# GSM_Schematic.net
KiCad netlist of a schematic drawn in EAGLE
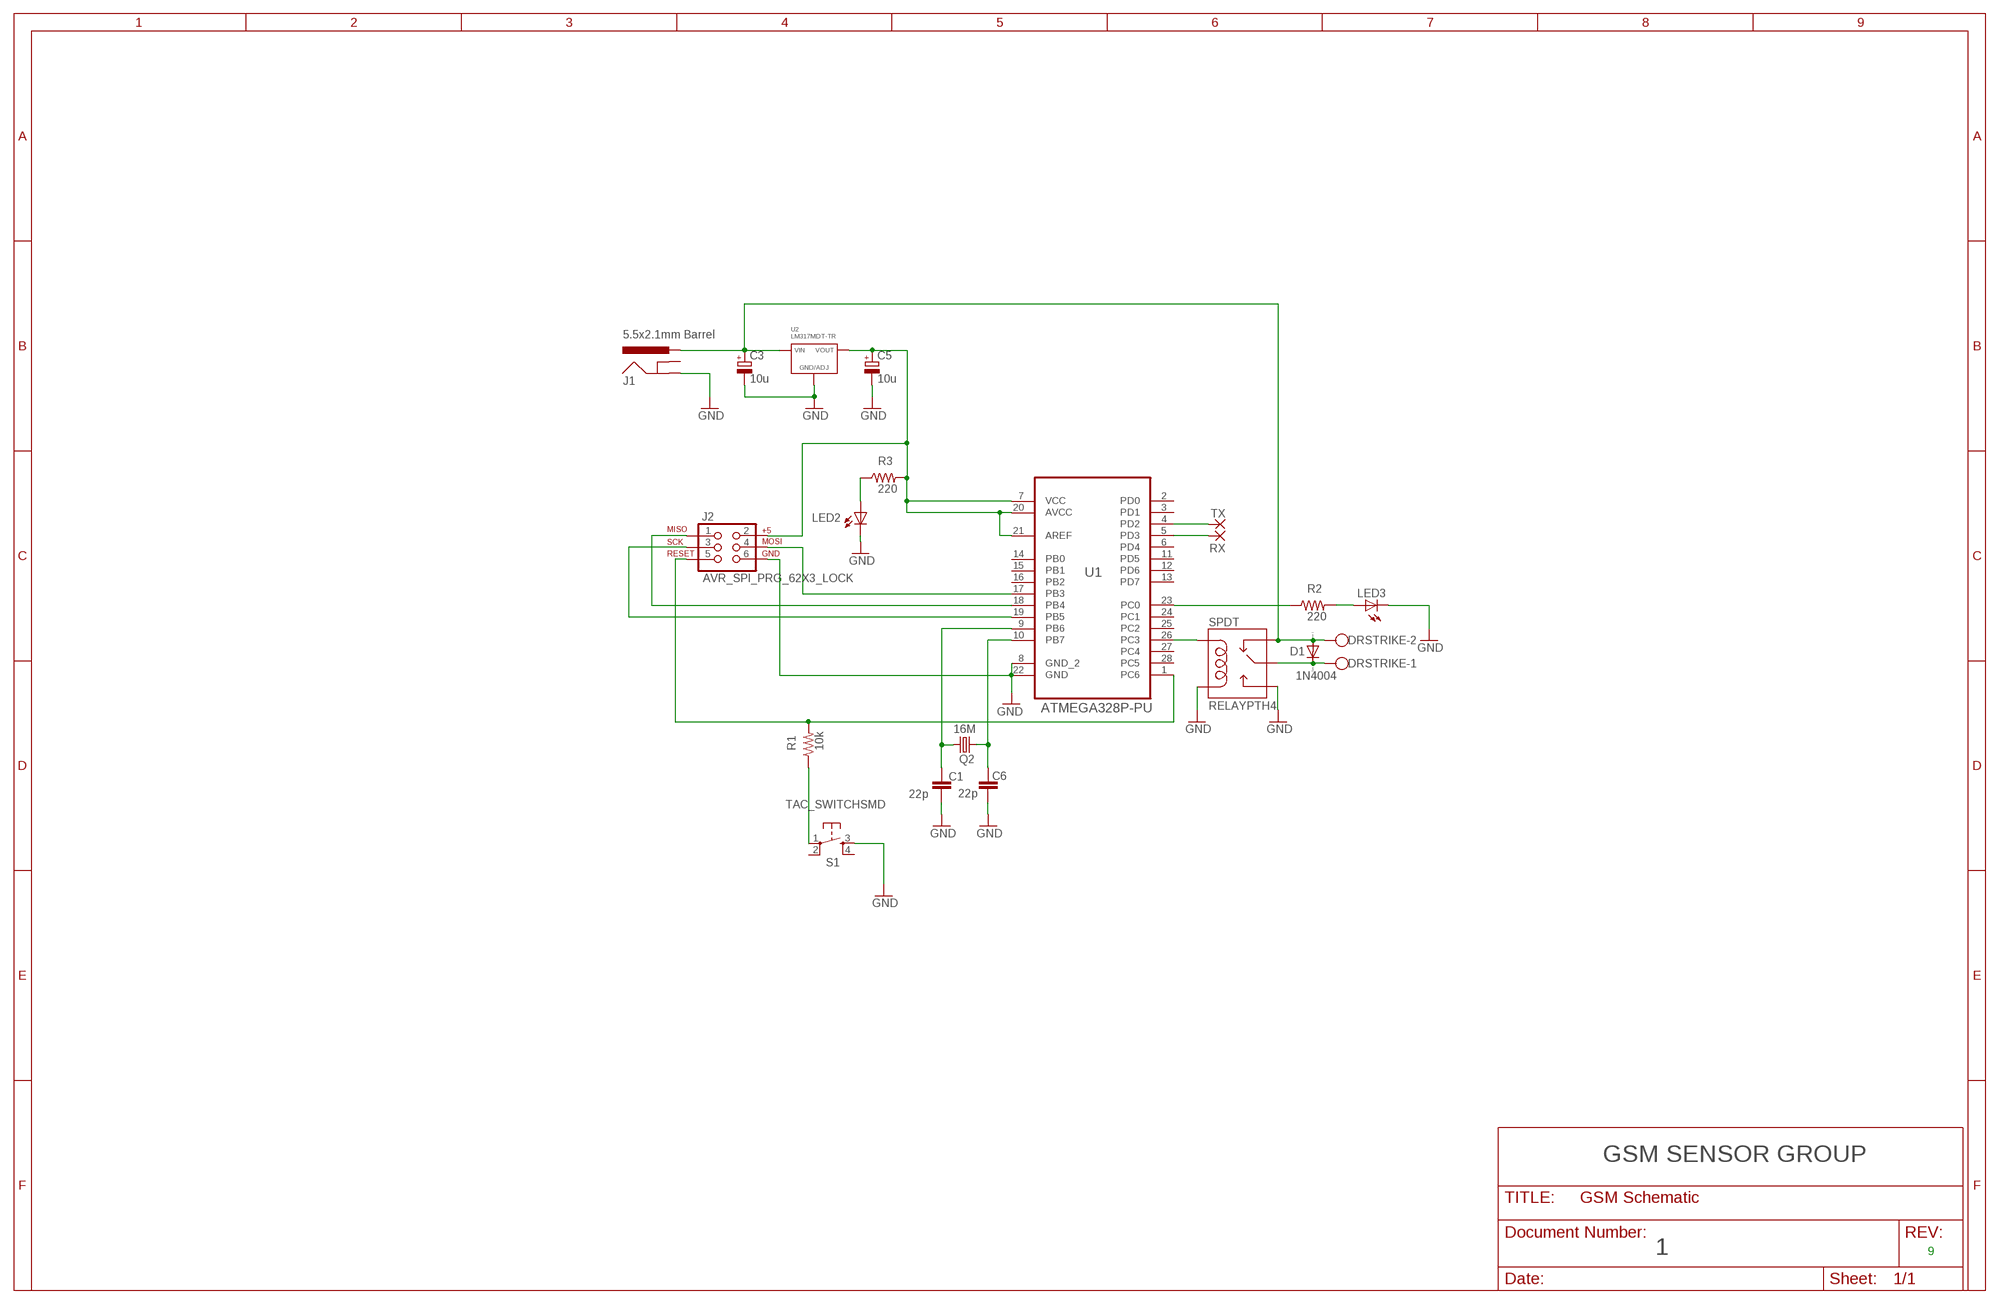
[diagram p0: schematic, sheet 1]

(export (version "E")
  (design (tool "Eeschema 10.0.6"))
  (components
    (comp (ref "C1")
      (value "22p")
      (footprint "eagle-import:C0603")
      (libsource (lib "eagle-import") (part "C-EUC0603"))
    )
    (comp (ref "C3")
      (value "10u")
      (footprint "eagle-import:E5-10,5")
      (libsource (lib "eagle-import") (part "CPOL-EUE5-10.5"))
    )
    (comp (ref "C5")
      (value "10u")
      (footprint "eagle-import:E5-10,5")
      (libsource (lib "eagle-import") (part "CPOL-EUE5-10.5"))
    )
    (comp (ref "C6")
      (value "22p")
      (footprint "eagle-import:C0603")
      (libsource (lib "eagle-import") (part "C-EUC0603"))
    )
    (comp (ref "D1")
      (value "1N4004")
      (footprint "eagle-import:DO41-10")
      (libsource (lib "eagle-import") (part "1N4004"))
    )
    (comp (ref "DRSTRIKE")
      (value "W237-102")
      (footprint "eagle-import:W237-102")
      (fields (field (name "MPN") "237-102"))
      (libsource (lib "eagle-import") (part "W237-102"))
    )
    (comp (ref "J1")
      (value "5.5x2.1mm Barrel")
      (footprint "eagle-import:POWER_JACK_SMD")
      (libsource (lib "eagle-import") (part "POWER_JACKSMD"))
    )
    (comp (ref "J2")
      (value "AVR_SPI_PRG_62X3_LOCK")
      (footprint "eagle-import:2X3_LOCK")
      (libsource (lib "eagle-import") (part "AVR_SPI_PRG_62X3_LOCK"))
    )
    (comp (ref "LED2")
      (value "LEDSML0603")
      (footprint "eagle-import:SML0603")
      (libsource (lib "eagle-import") (part "LEDSML0603"))
    )
    (comp (ref "LED3")
      (value "LED5MM")
      (footprint "eagle-import:LED5MM")
      (libsource (lib "eagle-import") (part "LED5MM"))
    )
    (comp (ref "Q2")
      (value "16M")
      (footprint "eagle-import:HC49UP")
      (libsource (lib "eagle-import") (part "CRYSTALHC49UP"))
    )
    (comp (ref "R1")
      (value "10k")
      (footprint "eagle-import:R0603")
      (libsource (lib "eagle-import") (part "R-US_R0603"))
    )
    (comp (ref "R2")
      (value "220")
      (footprint "eagle-import:R0603")
      (libsource (lib "eagle-import") (part "R-US_R0603"))
    )
    (comp (ref "R3")
      (value "220")
      (footprint "eagle-import:R0603")
      (libsource (lib "eagle-import") (part "R-US_R0603"))
    )
    (comp (ref "RX")
      (value "2,54/0,9")
      (footprint "eagle-import:2,54_0,9")
      (libsource (lib "eagle-import") (part "2,54/0,9"))
    )
    (comp (ref "S1")
      (value "TAC_SWITCHSMD")
      (footprint "eagle-import:TACTILE-SWITCH-SMD")
      (libsource (lib "eagle-import") (part "TAC_SWITCHSMD"))
    )
    (comp (ref "SPDT")
      (value "RELAYPTH4")
      (footprint "eagle-import:RELAY-JZC")
      (libsource (lib "eagle-import") (part "RELAYPTH4"))
    )
    (comp (ref "TX")
      (value "2,54/0,9")
      (footprint "eagle-import:2,54_0,9")
      (libsource (lib "eagle-import") (part "2,54/0,9"))
    )
    (comp (ref "U1")
      (value "ATMEGA328P-PU")
      (footprint "eagle-import:DIP254P762X457-28")
      (libsource (lib "eagle-import") (part "ATMEGA328P-PU"))
    )
    (comp (ref "U2")
      (value "LM317MDT-TR")
      (footprint "eagle-import:TO-252-3")
      (fields (field (name "HOUSEPART") "NO"))
      (libsource (lib "eagle-import") (part "LM317MDT-TR"))
    )
  )
  (nets
    (net (code "1") (name "GND") (class "Default")
      (node (ref "C1") (pin "2") (pinfunction "2_2") (pintype "passive"))
      (node (ref "C3") (pin "-") (pinfunction "-_-") (pintype "passive"))
      (node (ref "C5") (pin "-") (pinfunction "-_-") (pintype "passive"))
      (node (ref "C6") (pin "2") (pinfunction "2_2") (pintype "passive"))
      (node (ref "J1") (pin "P$4") (pinfunction "GND_P$4") (pintype "bidirectional"))
      (node (ref "J2") (pin "6") (pinfunction "6_6") (pintype "passive"))
      (node (ref "LED2") (pin "C") (pinfunction "C_C") (pintype "passive"))
      (node (ref "LED3") (pin "K") (pinfunction "C_K") (pintype "passive"))
      (node (ref "S1") (pin "3") (pinfunction "3_3") (pintype "passive"))
      (node (ref "SPDT") (pin "1") (pinfunction "COIL2_1") (pintype "bidirectional"))
      (node (ref "SPDT") (pin "3") (pinfunction "NO_3") (pintype "bidirectional"))
      (node (ref "U1") (pin "22") (pinfunction "GND_22") (pintype "passive"))
      (node (ref "U1") (pin "8") (pinfunction "GND_2_8") (pintype "passive"))
      (node (ref "U2") (pin "1") (pinfunction "GND/ADJ_1") (pintype "bidirectional"))
    )
    (net (code "2") (name "Net-(DRSTRIKEA-KL)") (class "Default")
      (node (ref "D1") (pin "C") (pinfunction "C_C") (pintype "passive"))
      (node (ref "DRSTRIKE") (pin "1") (pinfunction "KL_1") (pintype "passive"))
      (node (ref "SPDT") (pin "4") (pinfunction "MAIN_4") (pintype "bidirectional"))
    )
    (net (code "3") (name "Net-(DRSTRIKEB-KL)") (class "Default")
      (node (ref "C3") (pin "+") (pinfunction "+_+") (pintype "passive"))
      (node (ref "D1") (pin "A") (pinfunction "A_A") (pintype "passive"))
      (node (ref "DRSTRIKE") (pin "2") (pinfunction "KL_2") (pintype "passive"))
      (node (ref "J1") (pin "VIN0") (pinfunction "PWR_VIN0") (pintype "bidirectional"))
      (node (ref "SPDT") (pin "2") (pinfunction "NC_2") (pintype "bidirectional"))
      (node (ref "U2") (pin "2") (pinfunction "VIN_2") (pintype "bidirectional"))
    )
    (net (code "4") (name "Net-(LED2-PadA)") (class "Default")
      (node (ref "LED2") (pin "A") (pinfunction "A_A") (pintype "passive"))
      (node (ref "R3") (pin "1") (pinfunction "1_1") (pintype "passive"))
    )
    (net (code "5") (name "Net-(LED3-PadA)") (class "Default")
      (node (ref "LED3") (pin "A") (pinfunction "A_A") (pintype "passive"))
      (node (ref "R2") (pin "2") (pinfunction "2_2") (pintype "passive"))
    )
    (net (code "6") (name "Net-(R1-Pad1)") (class "Default")
      (node (ref "R1") (pin "1") (pinfunction "1_1") (pintype "passive"))
      (node (ref "S1") (pin "1") (pinfunction "1_1") (pintype "passive"))
    )
    (net (code "7") (name "Net-(RX-P)") (class "Default")
      (node (ref "RX") (pin "1") (pinfunction "P_1") (pintype "passive"))
      (node (ref "U1") (pin "5") (pinfunction "PD3_5") (pintype "bidirectional"))
    )
    (net (code "8") (name "Net-(SPDT-COIL1)") (class "Default")
      (node (ref "SPDT") (pin "5") (pinfunction "COIL1_5") (pintype "bidirectional"))
      (node (ref "U1") (pin "26") (pinfunction "PC3_26") (pintype "bidirectional"))
    )
    (net (code "9") (name "Net-(TX-P)") (class "Default")
      (node (ref "TX") (pin "1") (pinfunction "P_1") (pintype "passive"))
      (node (ref "U1") (pin "4") (pinfunction "PD2_4") (pintype "bidirectional"))
    )
    (net (code "10") (name "Net-(U1-AREF)") (class "Default")
      (node (ref "C5") (pin "+") (pinfunction "+_+") (pintype "passive"))
      (node (ref "J2") (pin "2") (pinfunction "2_2") (pintype "passive"))
      (node (ref "R3") (pin "2") (pinfunction "2_2") (pintype "passive"))
      (node (ref "U1") (pin "20") (pinfunction "AVCC_20") (pintype "power_in"))
      (node (ref "U1") (pin "21") (pinfunction "AREF_21") (pintype "input"))
      (node (ref "U1") (pin "7") (pinfunction "VCC_7") (pintype "power_in"))
      (node (ref "U2") (pin "PAD") (pinfunction "VOUT_PAD") (pintype "bidirectional"))
    )
    (net (code "11") (name "Net-(U1-PB3)") (class "Default")
      (node (ref "J2") (pin "4") (pinfunction "4_4") (pintype "passive"))
      (node (ref "U1") (pin "17") (pinfunction "PB3_17") (pintype "bidirectional"))
    )
    (net (code "12") (name "Net-(U1-PB4)") (class "Default")
      (node (ref "J2") (pin "1") (pinfunction "1_1") (pintype "passive"))
      (node (ref "U1") (pin "18") (pinfunction "PB4_18") (pintype "bidirectional"))
    )
    (net (code "13") (name "Net-(U1-PB5)") (class "Default")
      (node (ref "J2") (pin "3") (pinfunction "3_3") (pintype "passive"))
      (node (ref "U1") (pin "19") (pinfunction "PB5_19") (pintype "bidirectional"))
    )
    (net (code "14") (name "Net-(U1-PB6)") (class "Default")
      (node (ref "C1") (pin "1") (pinfunction "1_1") (pintype "passive"))
      (node (ref "Q2") (pin "2") (pinfunction "2_2") (pintype "passive"))
      (node (ref "U1") (pin "9") (pinfunction "PB6_9") (pintype "bidirectional"))
    )
    (net (code "15") (name "Net-(U1-PB7)") (class "Default")
      (node (ref "C6") (pin "1") (pinfunction "1_1") (pintype "passive"))
      (node (ref "Q2") (pin "1") (pinfunction "1_1") (pintype "passive"))
      (node (ref "U1") (pin "10") (pinfunction "PB7_10") (pintype "bidirectional"))
    )
    (net (code "16") (name "Net-(U1-PC0)") (class "Default")
      (node (ref "R2") (pin "1") (pinfunction "1_1") (pintype "passive"))
      (node (ref "U1") (pin "23") (pinfunction "PC0_23") (pintype "bidirectional"))
    )
    (net (code "17") (name "Net-(U1-PC6)") (class "Default")
      (node (ref "J2") (pin "5") (pinfunction "5_5") (pintype "passive"))
      (node (ref "R1") (pin "2") (pinfunction "2_2") (pintype "passive"))
      (node (ref "U1") (pin "1") (pinfunction "PC6_1") (pintype "bidirectional"))
    )
    (net (code "18") (name "unconnected-(J1-GNDBREAK-PadGND)") (class "Default")
      (node (ref "J1") (pin "GND") (pinfunction "GNDBREAK_GND") (pintype "bidirectional"))
    )
    (net (code "19") (name "unconnected-(S1-Pad2)") (class "Default")
      (node (ref "S1") (pin "2") (pinfunction "2_2") (pintype "passive"))
    )
    (net (code "20") (name "unconnected-(S1-Pad4)") (class "Default")
      (node (ref "S1") (pin "4") (pinfunction "4_4") (pintype "passive"))
    )
    (net (code "21") (name "unconnected-(U1-PB0-Pad14)") (class "Default")
      (node (ref "U1") (pin "14") (pinfunction "PB0_14") (pintype "bidirectional"))
    )
    (net (code "22") (name "unconnected-(U1-PB1-Pad15)") (class "Default")
      (node (ref "U1") (pin "15") (pinfunction "PB1_15") (pintype "bidirectional"))
    )
    (net (code "23") (name "unconnected-(U1-PB2-Pad16)") (class "Default")
      (node (ref "U1") (pin "16") (pinfunction "PB2_16") (pintype "bidirectional"))
    )
    (net (code "24") (name "unconnected-(U1-PC1-Pad24)") (class "Default")
      (node (ref "U1") (pin "24") (pinfunction "PC1_24") (pintype "bidirectional"))
    )
    (net (code "25") (name "unconnected-(U1-PC2-Pad25)") (class "Default")
      (node (ref "U1") (pin "25") (pinfunction "PC2_25") (pintype "bidirectional"))
    )
    (net (code "26") (name "unconnected-(U1-PC4-Pad27)") (class "Default")
      (node (ref "U1") (pin "27") (pinfunction "PC4_27") (pintype "bidirectional"))
    )
    (net (code "27") (name "unconnected-(U1-PC5-Pad28)") (class "Default")
      (node (ref "U1") (pin "28") (pinfunction "PC5_28") (pintype "bidirectional"))
    )
    (net (code "28") (name "unconnected-(U1-PD0-Pad2)") (class "Default")
      (node (ref "U1") (pin "2") (pinfunction "PD0_2") (pintype "bidirectional"))
    )
    (net (code "29") (name "unconnected-(U1-PD1-Pad3)") (class "Default")
      (node (ref "U1") (pin "3") (pinfunction "PD1_3") (pintype "bidirectional"))
    )
    (net (code "30") (name "unconnected-(U1-PD4-Pad6)") (class "Default")
      (node (ref "U1") (pin "6") (pinfunction "PD4_6") (pintype "bidirectional"))
    )
    (net (code "31") (name "unconnected-(U1-PD5-Pad11)") (class "Default")
      (node (ref "U1") (pin "11") (pinfunction "PD5_11") (pintype "bidirectional"))
    )
    (net (code "32") (name "unconnected-(U1-PD6-Pad12)") (class "Default")
      (node (ref "U1") (pin "12") (pinfunction "PD6_12") (pintype "bidirectional"))
    )
    (net (code "33") (name "unconnected-(U1-PD7-Pad13)") (class "Default")
      (node (ref "U1") (pin "13") (pinfunction "PD7_13") (pintype "bidirectional"))
    )
  )
)
